# Sensor_Modules.net
KiCad netlist of a schematic drawn in Altium Designer
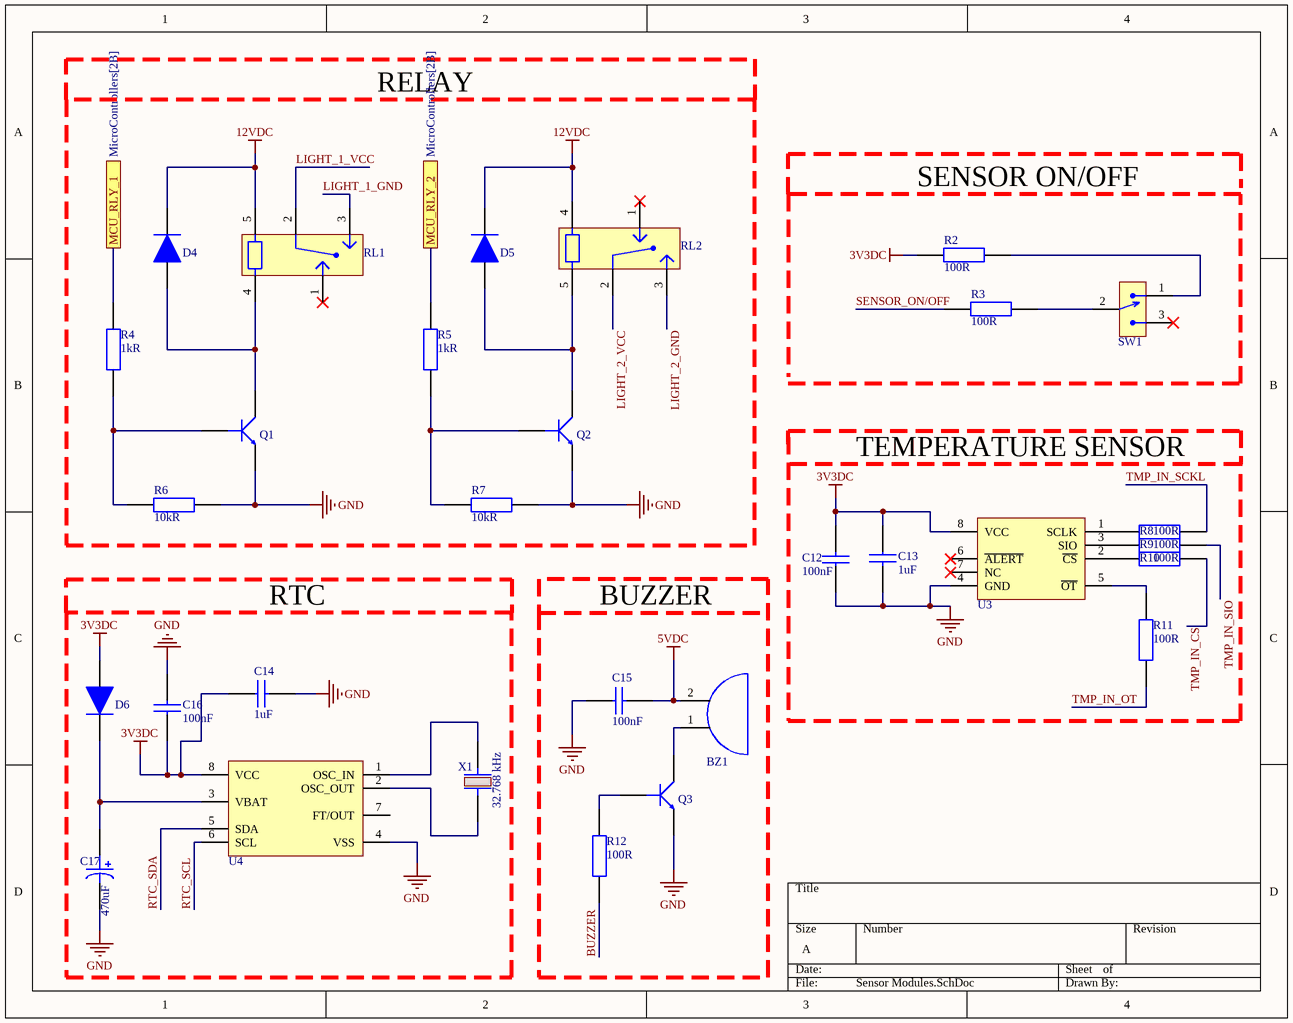
[diagram p0: Sensor Modules.SchDoc]

(export (version "E")
  (design (tool "Eeschema 10.0.6"))
  (components
    (comp (ref "BZ1")
      (value "CMI-9605IC-0580T")
      (footprint "CMI-9605IC")
      (description "Buzzers Indicator, Internally Driven Magnetic 5V 30mA 2.7kHz 80dB @ 5V, 10cm Through Hole PC Pins")
      (fields (field (name "MANUFACTURER") "CUI Devices") (field (name "DESIGNED BY") "BERK"))
      (libsource (lib "UDEMY_Library") (part "CMI-9605IC-0580T"))
    )
    (comp (ref "C12")
      (value "CL21B104KBCNNNC")
      (footprint "CAP_0805")
      (description "CAP CER 100nF %10 0805")
      (fields
        (field (name "MANUFACTURER") "Samsung")
        (field (name "TOLERANCE") "10%")
        (field (name "CAPACITANCE") "100nF")
        (field (name "DESIGNED BY") "BERK")
      )
      (libsource (lib "UDEMY_Library") (part "CAP CER 100nF 0805"))
    )
    (comp (ref "C13")
      (value "CL21B105KBFNNNE")
      (footprint "CAP_0805")
      (description "CAP CER 1uF %10 0805")
      (fields
        (field (name "MANUFACTURER") "Samsung")
        (field (name "TOLERANCE") "10%")
        (field (name "CAPACITANCE") "1uF")
        (field (name "DESIGNED BY") "BERK")
      )
      (libsource (lib "UDEMY_Library") (part "CAP CER 1uF 0805"))
    )
    (comp (ref "C14")
      (value "CL21B105KBFNNNE")
      (footprint "CAP_0805")
      (description "CAP CER 1uF %10 0805")
      (fields
        (field (name "MANUFACTURER") "Samsung")
        (field (name "TOLERANCE") "10%")
        (field (name "CAPACITANCE") "1uF")
        (field (name "DESIGNED BY") "BERK")
      )
      (libsource (lib "UDEMY_Library") (part "CAP CER 1uF 0805"))
    )
    (comp (ref "C15")
      (value "C0603C104K5RACTU")
      (footprint "CAP_0603")
      (description "CAP CER 100nF %10 0603 SMD")
      (fields
        (field (name "MANUFACTURER") "KEMET")
        (field (name "TOLERANCE") "10%")
        (field (name "CAPACITANCE") "100nF")
        (field (name "DESIGNED BY") "BERK")
      )
      (libsource (lib "UDEMY_Library") (part "CAP CER 100nF 0603"))
    )
    (comp (ref "C16")
      (value "CL21B104KBCNNNC")
      (footprint "CAP_0805")
      (description "CAP CER 100nF %10 0805")
      (fields
        (field (name "MANUFACTURER") "Samsung")
        (field (name "TOLERANCE") "10%")
        (field (name "CAPACITANCE") "100nF")
        (field (name "DESIGNED BY") "BERK")
      )
      (libsource (lib "UDEMY_Library") (part "CAP CER 100nF 0805"))
    )
    (comp (ref "C17")
      (value "ESH477M050AH4AA")
      (footprint "CAP_RADIAL_D10_P5")
      (description "CAP ALU ELEC 470uF 50V RADIAL")
      (fields
        (field (name "MANUFACTURER") "KEMET")
        (field (name "TOLERANCE") "20%")
        (field (name "CAPACITANCE") "470uF")
        (field (name "DESIGNED BY") "BERK")
      )
      (libsource (lib "UDEMY_Library") (part "CAP ALU ELEC 470uF 50V"))
    )
    (comp (ref "D4")
      (value "1N4148WS")
      (footprint "SOD323F")
      (description "Diode, Single, 75 V, 150 mA, 1 V, 4 ns")
      (fields
        (field (name "MANUFACTURER") "ON Semiconductor / Fairchild")
        (field (name "DESIGNED BY") "BERK")
      )
      (libsource (lib "UDEMY_Library") (part "1N4148WS"))
    )
    (comp (ref "D5")
      (value "1N4148WS")
      (footprint "SOD323F")
      (description "Diode, Single, 75 V, 150 mA, 1 V, 4 ns")
      (fields
        (field (name "MANUFACTURER") "ON Semiconductor / Fairchild")
        (field (name "DESIGNED BY") "BERK")
      )
      (libsource (lib "UDEMY_Library") (part "1N4148WS"))
    )
    (comp (ref "D6")
      (value "1N4148WS")
      (footprint "SOD323F")
      (description "Diode, Single, 75 V, 150 mA, 1 V, 4 ns")
      (fields
        (field (name "MANUFACTURER") "ON Semiconductor / Fairchild")
        (field (name "DESIGNED BY") "BERK")
      )
      (libsource (lib "UDEMY_Library") (part "1N4148WS"))
    )
    (comp (ref "Q1")
      (value "MMBT3904-7-F")
      (footprint "SOT-23F")
      (description "Transistor General Purpose BJT NPN 40 Volt 0.2A Automotive 3-Pin SOT-23")
      (fields (field (name "MANUFACTURER") "Diodes Zetex") (field (name "DESIGNED BY") "BERK"))
      (libsource (lib "UDEMY_Library") (part "MMBT3904-7-F"))
    )
    (comp (ref "Q2")
      (value "MMBT3904-7-F")
      (footprint "SOT-23F")
      (description "Transistor General Purpose BJT NPN 40 Volt 0.2A Automotive 3-Pin SOT-23")
      (fields (field (name "MANUFACTURER") "Diodes Zetex") (field (name "DESIGNED BY") "BERK"))
      (libsource (lib "UDEMY_Library") (part "MMBT3904-7-F"))
    )
    (comp (ref "Q3")
      (value "MMBT3904-7-F")
      (footprint "SOT-23F")
      (description "Transistor General Purpose BJT NPN 40 Volt 0.2A Automotive 3-Pin SOT-23")
      (fields (field (name "MANUFACTURER") "Diodes Zetex") (field (name "DESIGNED BY") "BERK"))
      (libsource (lib "UDEMY_Library") (part "MMBT3904-7-F"))
    )
    (comp (ref "R2")
      (value "RC0603JR-07100RL")
      (footprint "RES_0603")
      (description "RES 100 %5 OHM 0603 SMD")
      (fields
        (field (name "MANUFACTURER") "Yageo")
        (field (name "TOLERANCE") "5%")
        (field (name "RESISTANCE") "100R")
        (field (name "DESIGNED BY") "BERK")
      )
      (libsource (lib "UDEMY_Library") (part "RES 100 OHM 0603"))
    )
    (comp (ref "R3")
      (value "RC0603JR-07100RL")
      (footprint "RES_0603")
      (description "RES 100 %5 OHM 0603 SMD")
      (fields
        (field (name "MANUFACTURER") "Yageo")
        (field (name "TOLERANCE") "5%")
        (field (name "RESISTANCE") "100R")
        (field (name "DESIGNED BY") "BERK")
      )
      (libsource (lib "UDEMY_Library") (part "RES 100 OHM 0603"))
    )
    (comp (ref "R4")
      (value "RC0603FR-0710KL")
      (footprint "RES_0603")
      (description "RES 1K %1 OHM 0603 SMD")
      (fields
        (field (name "MANUFACTURER") "Yageo")
        (field (name "MANUFACTURER PART NUMBER") "RC0603JR-071KL")
        (field (name "RESISTANCE") "1kR")
        (field (name "DESIGNED BY") "BERK")
      )
      (libsource (lib "UDEMY_Library") (part "RES 1K OHM 0603"))
    )
    (comp (ref "R5")
      (value "RC0603FR-0710KL")
      (footprint "RES_0603")
      (description "RES 1K %1 OHM 0603 SMD")
      (fields
        (field (name "MANUFACTURER") "Yageo")
        (field (name "MANUFACTURER PART NUMBER") "RC0603JR-071KL")
        (field (name "RESISTANCE") "1kR")
        (field (name "DESIGNED BY") "BERK")
      )
      (libsource (lib "UDEMY_Library") (part "RES 1K OHM 0603"))
    )
    (comp (ref "R6")
      (value "RC0603FR-0710KL")
      (footprint "RES_0603")
      (description "RES 10K %1 OHM 0603 SMD")
      (fields
        (field (name "MANUFACTURER") "Yageo")
        (field (name "TOLERANCE") "1%")
        (field (name "RESISTANCE") "10kR")
        (field (name "DESIGNED BY") "BERK")
      )
      (libsource (lib "UDEMY_Library") (part "RES 10K OHM 0603"))
    )
    (comp (ref "R7")
      (value "RC0603FR-0710KL")
      (footprint "RES_0603")
      (description "RES 10K %1 OHM 0603 SMD")
      (fields
        (field (name "MANUFACTURER") "Yageo")
        (field (name "TOLERANCE") "1%")
        (field (name "RESISTANCE") "10kR")
        (field (name "DESIGNED BY") "BERK")
      )
      (libsource (lib "UDEMY_Library") (part "RES 10K OHM 0603"))
    )
    (comp (ref "R8")
      (value "RC0603JR-07100RL")
      (footprint "RES_0603")
      (description "RES 100 %5 OHM 0603 SMD")
      (fields
        (field (name "MANUFACTURER") "Yageo")
        (field (name "TOLERANCE") "5%")
        (field (name "RESISTANCE") "100R")
        (field (name "DESIGNED BY") "BERK")
      )
      (libsource (lib "") (part "RES 100 OHM 0603_1"))
    )
    (comp (ref "R9")
      (value "RC0603JR-07100RL")
      (footprint "RES_0603")
      (description "RES 100 %5 OHM 0603 SMD")
      (fields
        (field (name "MANUFACTURER") "Yageo")
        (field (name "TOLERANCE") "5%")
        (field (name "RESISTANCE") "100R")
        (field (name "DESIGNED BY") "BERK")
      )
      (libsource (lib "") (part "RES 100 OHM 0603_1"))
    )
    (comp (ref "R10")
      (value "RC0603JR-07100RL")
      (footprint "RES_0603")
      (description "RES 100 %5 OHM 0603 SMD")
      (fields
        (field (name "MANUFACTURER") "Yageo")
        (field (name "TOLERANCE") "5%")
        (field (name "RESISTANCE") "100R")
        (field (name "DESIGNED BY") "BERK")
      )
      (libsource (lib "") (part "RES 100 OHM 0603_1"))
    )
    (comp (ref "R11")
      (value "RC0603JR-07100RL")
      (footprint "RES_0603")
      (description "RES 100 %5 OHM 0603 SMD")
      (fields
        (field (name "MANUFACTURER") "Yageo")
        (field (name "TOLERANCE") "5%")
        (field (name "RESISTANCE") "100R")
        (field (name "DESIGNED BY") "BERK")
      )
      (libsource (lib "") (part "RES 100 OHM 0603_2"))
    )
    (comp (ref "R12")
      (value "RC0603JR-07100RL")
      (footprint "RES_0603")
      (description "RES 100 %5 OHM 0603 SMD")
      (fields
        (field (name "MANUFACTURER") "Yageo")
        (field (name "TOLERANCE") "5%")
        (field (name "RESISTANCE") "100R")
        (field (name "DESIGNED BY") "BERK")
      )
      (libsource (lib "") (part "RES 100 OHM 0603_2"))
    )
    (comp (ref "RL1")
      (value "ALQ112")
      (footprint "ALQ112")
      (description "General Purpose Relay SPDT (1 Form C) 12VDC Coil Through Hole")
      (fields (field (name "MANUFACTURER") "Panasonic") (field (name "DESIGNED BY") "BERK"))
      (libsource (lib "UDEMY_Library") (part "ALQ112"))
    )
    (comp (ref "RL2")
      (value "ALQ112")
      (footprint "ALQ112")
      (description "General Purpose Relay SPDT (1 Form C) 12VDC Coil Through Hole")
      (fields (field (name "MANUFACTURER") "Panasonic") (field (name "DESIGNED BY") "BERK"))
      (libsource (lib "") (part "ALQ112_1"))
    )
    (comp (ref "SW1")
      (value "EG1215AA")
      (footprint "EG1215AA")
      (description "Slide Switch, SPDT, 0.025A, 24V, SMD")
      (fields
        (field (name "MANUFACTURER") "E-Switch")
        (field (name "TOLERANCE") "4.95%")
        (field (name "DESIGNED BY") "BERK")
      )
      (libsource (lib "UDEMY_Library") (part "EG1215AA"))
    )
    (comp (ref "U3")
      (value "MAX6662")
      (footprint "SOIC8")
      (description "SENSOR TEMPERATURE SPI 8SOIC")
      (fields
        (field (name "MANUFACTURER") "Maxim")
        (field (name "MANUFACTURER PART NUMBER") "MAX6662MSA+")
        (field (name "DESIGNED BY") "BERK")
      )
      (libsource (lib "UDEMY_Library") (part "MAX6662"))
    )
    (comp (ref "U4")
      (value "M41T00M6F")
      (footprint "SOIC8")
      (description "IC RTC CLK/CALENDAR I2C 8-SOIC")
      (fields (field (name "MANUFACTURER") "STMicroelectronics") (field (name "DESIGNED BY") "BERK"))
      (libsource (lib "UDEMY_Library") (part "M41T00M6F"))
    )
    (comp (ref "X1")
      (value "ABS05-32.768KHZ-T")
      (footprint "ABS05")
      (description "Crystal, 32.768 kHz, SMD, 1.6mm x 1mm, 12.5 pF, 20 ppm, ABS05 Series")
      (fields
        (field (name "MANUFACTURER") "Abracon")
        (field (name "TOLERANCE") "20ppm")
        (field (name "OPERATING FREQUENCY") "32.768 kHz")
        (field (name "DESIGNED BY") "BERK")
      )
      (libsource (lib "UDEMY_Library") (part "CRYSTAL 32768kHZ"))
    )
  )
  (nets
    (net (code "1") (name "/BUZZER") (class "Default")
      (node (ref "R12") (pin "1") (pinfunction "1_1") (pintype "passive"))
    )
    (net (code "2") (name "/LIGHT_1_GND") (class "Default")
      (node (ref "RL1") (pin "3") (pinfunction "3_3") (pintype "passive"))
    )
    (net (code "3") (name "/LIGHT_1_VCC") (class "Default")
      (node (ref "RL1") (pin "2") (pinfunction "2_2") (pintype "passive"))
    )
    (net (code "4") (name "/LIGHT_2_GND") (class "Default")
      (node (ref "RL2") (pin "3") (pinfunction "3_3") (pintype "passive"))
    )
    (net (code "5") (name "/LIGHT_2_VCC") (class "Default")
      (node (ref "RL2") (pin "2") (pinfunction "2_2") (pintype "passive"))
    )
    (net (code "6") (name "/MCU_RLY_1") (class "Default")
      (node (ref "R4") (pin "2") (pinfunction "2_2") (pintype "passive"))
    )
    (net (code "7") (name "/MCU_RLY_2") (class "Default")
      (node (ref "R5") (pin "2") (pinfunction "2_2") (pintype "passive"))
    )
    (net (code "8") (name "/RTC_SCL") (class "Default")
      (node (ref "U4") (pin "6") (pinfunction "SCL_6") (pintype "passive"))
    )
    (net (code "9") (name "/RTC_SDA") (class "Default")
      (node (ref "U4") (pin "5") (pinfunction "SDA_5") (pintype "passive"))
    )
    (net (code "10") (name "/SENSOR_ON{slash}OFF") (class "Default")
      (node (ref "R3") (pin "1") (pinfunction "1_1") (pintype "passive"))
    )
    (net (code "11") (name "/TMP_IN_CS") (class "Default")
      (node (ref "R10") (pin "1") (pinfunction "1_1") (pintype "passive"))
    )
    (net (code "12") (name "/TMP_IN_OT") (class "Default")
      (node (ref "R11") (pin "1") (pinfunction "1_1") (pintype "passive"))
    )
    (net (code "13") (name "/TMP_IN_SCKL") (class "Default")
      (node (ref "R8") (pin "1") (pinfunction "1_1") (pintype "passive"))
    )
    (net (code "14") (name "/TMP_IN_SIO") (class "Default")
      (node (ref "R9") (pin "1") (pinfunction "1_1") (pintype "passive"))
    )
    (net (code "15") (name "3V3DC") (class "Default")
      (node (ref "C12") (pin "2") (pinfunction "2_2") (pintype "passive"))
      (node (ref "C13") (pin "1") (pinfunction "1_1") (pintype "passive"))
      (node (ref "C14") (pin "1") (pinfunction "1_1") (pintype "passive"))
      (node (ref "C16") (pin "1") (pinfunction "1_1") (pintype "passive"))
      (node (ref "D6") (pin "2") (pinfunction "2_2") (pintype "power_in"))
      (node (ref "R2") (pin "1") (pinfunction "1_1") (pintype "passive"))
      (node (ref "U3") (pin "8") (pinfunction "VCC_8") (pintype "passive"))
      (node (ref "U4") (pin "8") (pinfunction "VCC_8") (pintype "passive"))
    )
    (net (code "16") (name "5VDC") (class "Default")
      (node (ref "BZ1") (pin "2") (pinfunction "2_2") (pintype "passive"))
      (node (ref "C15") (pin "2") (pinfunction "2_2") (pintype "passive"))
    )
    (net (code "17") (name "12VDC") (class "Default")
      (node (ref "D4") (pin "1") (pinfunction "1_1") (pintype "power_in"))
      (node (ref "D5") (pin "1") (pinfunction "1_1") (pintype "power_in"))
      (node (ref "RL1") (pin "5") (pinfunction "5_5") (pintype "passive"))
      (node (ref "RL2") (pin "4") (pinfunction "4_4") (pintype "passive"))
    )
    (net (code "18") (name "GND") (class "Default")
      (node (ref "C12") (pin "1") (pinfunction "1_1") (pintype "passive"))
      (node (ref "C13") (pin "2") (pinfunction "2_2") (pintype "passive"))
      (node (ref "C14") (pin "2") (pinfunction "2_2") (pintype "passive"))
      (node (ref "C15") (pin "1") (pinfunction "1_1") (pintype "passive"))
      (node (ref "C16") (pin "2") (pinfunction "2_2") (pintype "passive"))
      (node (ref "C17") (pin "2") (pinfunction "2_2") (pintype "passive"))
      (node (ref "Q1") (pin "2") (pinfunction "E_2") (pintype "power_in"))
      (node (ref "Q2") (pin "2") (pinfunction "E_2") (pintype "power_in"))
      (node (ref "Q3") (pin "2") (pinfunction "E_2") (pintype "power_in"))
      (node (ref "R6") (pin "2") (pinfunction "2_2") (pintype "passive"))
      (node (ref "R7") (pin "2") (pinfunction "2_2") (pintype "passive"))
      (node (ref "U3") (pin "4") (pinfunction "GND_4") (pintype "passive"))
      (node (ref "U4") (pin "4") (pinfunction "VSS_4") (pintype "passive"))
    )
    (net (code "19") (name "Net-(Q1-B)") (class "Default")
      (node (ref "Q1") (pin "1") (pinfunction "B_1") (pintype "power_in"))
      (node (ref "R4") (pin "1") (pinfunction "1_1") (pintype "passive"))
      (node (ref "R6") (pin "1") (pinfunction "1_1") (pintype "passive"))
    )
    (net (code "20") (name "Net-(Q1-C)") (class "Default")
      (node (ref "D4") (pin "2") (pinfunction "2_2") (pintype "power_in"))
      (node (ref "Q1") (pin "3") (pinfunction "C_3") (pintype "power_in"))
      (node (ref "RL1") (pin "4") (pinfunction "4_4") (pintype "passive"))
    )
    (net (code "21") (name "Net-(Q2-B)") (class "Default")
      (node (ref "Q2") (pin "1") (pinfunction "B_1") (pintype "power_in"))
      (node (ref "R5") (pin "1") (pinfunction "1_1") (pintype "passive"))
      (node (ref "R7") (pin "1") (pinfunction "1_1") (pintype "passive"))
    )
    (net (code "22") (name "Net-(Q2-C)") (class "Default")
      (node (ref "D5") (pin "2") (pinfunction "2_2") (pintype "power_in"))
      (node (ref "Q2") (pin "3") (pinfunction "C_3") (pintype "power_in"))
      (node (ref "RL2") (pin "5") (pinfunction "5_5") (pintype "passive"))
    )
    (net (code "23") (name "Net-(Q3-B)") (class "Default")
      (node (ref "Q3") (pin "1") (pinfunction "B_1") (pintype "power_in"))
      (node (ref "R12") (pin "2") (pinfunction "2_2") (pintype "passive"))
    )
    (net (code "24") (name "Net-(Q3-C)") (class "Default")
      (node (ref "BZ1") (pin "1") (pinfunction "1_1") (pintype "passive"))
      (node (ref "Q3") (pin "3") (pinfunction "C_3") (pintype "power_in"))
    )
    (net (code "25") (name "Net-(R2-Pad2)") (class "Default")
      (node (ref "R2") (pin "2") (pinfunction "2_2") (pintype "passive"))
      (node (ref "SW1") (pin "1") (pinfunction "1_1") (pintype "passive"))
    )
    (net (code "26") (name "Net-(R3-Pad2)") (class "Default")
      (node (ref "R3") (pin "2") (pinfunction "2_2") (pintype "passive"))
      (node (ref "SW1") (pin "2") (pinfunction "2_2") (pintype "passive"))
    )
    (net (code "27") (name "Net-(U3-SCLK)") (class "Default")
      (node (ref "R8") (pin "2") (pinfunction "2_2") (pintype "passive"))
      (node (ref "U3") (pin "1") (pinfunction "SCLK_1") (pintype "passive"))
    )
    (net (code "28") (name "Net-(U3-SIO)") (class "Default")
      (node (ref "R9") (pin "2") (pinfunction "2_2") (pintype "passive"))
      (node (ref "U3") (pin "3") (pinfunction "SIO_3") (pintype "passive"))
    )
    (net (code "29") (name "Net-(U3-~{CS})") (class "Default")
      (node (ref "R10") (pin "2") (pinfunction "2_2") (pintype "passive"))
      (node (ref "U3") (pin "2") (pinfunction "~{CS}_2") (pintype "passive"))
    )
    (net (code "30") (name "Net-(U3-~{OT})") (class "Default")
      (node (ref "R11") (pin "2") (pinfunction "2_2") (pintype "passive"))
      (node (ref "U3") (pin "5") (pinfunction "~{OT}_5") (pintype "passive"))
    )
    (net (code "31") (name "Net-(U4-OSC_IN)") (class "Default")
      (node (ref "U4") (pin "1") (pinfunction "OSC_IN_1") (pintype "passive"))
      (node (ref "X1") (pin "2") (pinfunction "2_2") (pintype "passive"))
    )
    (net (code "32") (name "Net-(U4-OSC_OUT)") (class "Default")
      (node (ref "U4") (pin "2") (pinfunction "OSC_OUT_2") (pintype "passive"))
      (node (ref "X1") (pin "1") (pinfunction "1_1") (pintype "passive"))
    )
    (net (code "33") (name "Net-(U4-VBAT)") (class "Default")
      (node (ref "C17") (pin "1") (pinfunction "1_1") (pintype "passive"))
      (node (ref "D6") (pin "1") (pinfunction "1_1") (pintype "power_in"))
      (node (ref "U4") (pin "3") (pinfunction "VBAT_3") (pintype "passive"))
    )
    (net (code "34") (name "unconnected-(RL1-Pad1)") (class "Default")
      (node (ref "RL1") (pin "1") (pinfunction "1_1") (pintype "passive+no_connect"))
    )
    (net (code "35") (name "unconnected-(RL2-Pad1)") (class "Default")
      (node (ref "RL2") (pin "1") (pinfunction "1_1") (pintype "passive+no_connect"))
    )
    (net (code "36") (name "unconnected-(SW1-Pad3)") (class "Default")
      (node (ref "SW1") (pin "3") (pinfunction "3_3") (pintype "passive+no_connect"))
    )
    (net (code "37") (name "unconnected-(U3-NC-Pad7)") (class "Default")
      (node (ref "U3") (pin "7") (pinfunction "NC_7") (pintype "passive+no_connect"))
    )
    (net (code "38") (name "unconnected-(U3-~{ALERT}-Pad6)") (class "Default")
      (node (ref "U3") (pin "6") (pinfunction "~{ALERT}_6") (pintype "passive+no_connect"))
    )
    (net (code "39") (name "unconnected-(U4-FT{slash}OUT-Pad7)") (class "Default")
      (node (ref "U4") (pin "7") (pinfunction "FT/OUT_7") (pintype "passive"))
    )
  )
)
